# stepsticka4984.net
KiCad netlist of a schematic drawn in EAGLE
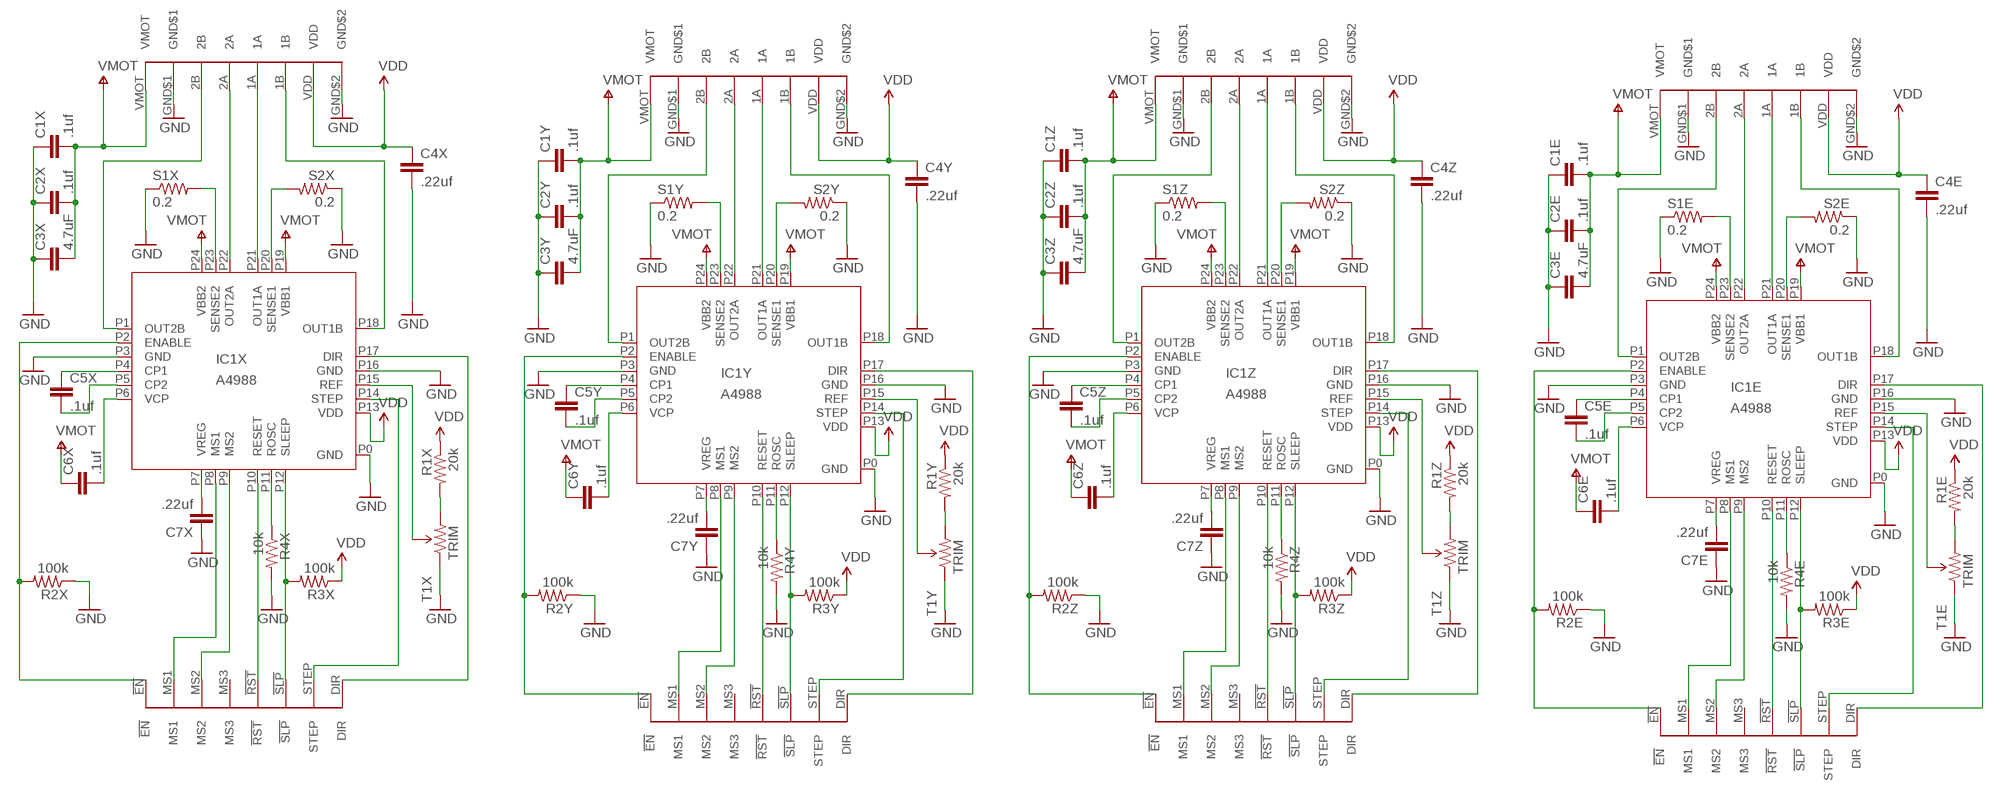
[diagram p0: schematic, sheet 1]

(export (version "E")
  (design (tool "Eeschema 10.0.6"))
  (components
    (comp (ref "C1E")
      (value ".1uf")
      (footprint "eagle-import:0402-CAP")
      (libsource (lib "eagle-import") (part "CAP0402-CAP"))
    )
    (comp (ref "C1X")
      (value ".1uf")
      (footprint "eagle-import:0402-CAP")
      (libsource (lib "eagle-import") (part "CAP0402-CAP"))
    )
    (comp (ref "C1Y")
      (value ".1uf")
      (footprint "eagle-import:0402-CAP")
      (libsource (lib "eagle-import") (part "CAP0402-CAP"))
    )
    (comp (ref "C1Z")
      (value ".1uf")
      (footprint "eagle-import:0402-CAP")
      (libsource (lib "eagle-import") (part "CAP0402-CAP"))
    )
    (comp (ref "C2E")
      (value ".1uf")
      (footprint "eagle-import:0402-CAP")
      (libsource (lib "eagle-import") (part "CAP0402-CAP"))
    )
    (comp (ref "C2X")
      (value ".1uf")
      (footprint "eagle-import:0402-CAP")
      (libsource (lib "eagle-import") (part "CAP0402-CAP"))
    )
    (comp (ref "C2Y")
      (value ".1uf")
      (footprint "eagle-import:0402-CAP")
      (libsource (lib "eagle-import") (part "CAP0402-CAP"))
    )
    (comp (ref "C2Z")
      (value ".1uf")
      (footprint "eagle-import:0402-CAP")
      (libsource (lib "eagle-import") (part "CAP0402-CAP"))
    )
    (comp (ref "C3E")
      (value "4.7uF")
      (footprint "eagle-import:1206")
      (libsource (lib "eagle-import") (part "CAP1206"))
    )
    (comp (ref "C3X")
      (value "4.7uF")
      (footprint "eagle-import:1206")
      (libsource (lib "eagle-import") (part "CAP1206"))
    )
    (comp (ref "C3Y")
      (value "4.7uF")
      (footprint "eagle-import:1206")
      (libsource (lib "eagle-import") (part "CAP1206"))
    )
    (comp (ref "C3Z")
      (value "4.7uF")
      (footprint "eagle-import:1206")
      (libsource (lib "eagle-import") (part "CAP1206"))
    )
    (comp (ref "C4E")
      (value ".22uf")
      (footprint "eagle-import:0402-CAP")
      (libsource (lib "eagle-import") (part "CAP0402-CAP"))
    )
    (comp (ref "C4X")
      (value ".22uf")
      (footprint "eagle-import:0402-CAP")
      (libsource (lib "eagle-import") (part "CAP0402-CAP"))
    )
    (comp (ref "C4Y")
      (value ".22uf")
      (footprint "eagle-import:0402-CAP")
      (libsource (lib "eagle-import") (part "CAP0402-CAP"))
    )
    (comp (ref "C4Z")
      (value ".22uf")
      (footprint "eagle-import:0402-CAP")
      (libsource (lib "eagle-import") (part "CAP0402-CAP"))
    )
    (comp (ref "C5E")
      (value ".1uf")
      (footprint "eagle-import:0402-CAP")
      (libsource (lib "eagle-import") (part "CAP0402-CAP"))
    )
    (comp (ref "C5X")
      (value ".1uf")
      (footprint "eagle-import:0402-CAP")
      (libsource (lib "eagle-import") (part "CAP0402-CAP"))
    )
    (comp (ref "C5Y")
      (value ".1uf")
      (footprint "eagle-import:0402-CAP")
      (libsource (lib "eagle-import") (part "CAP0402-CAP"))
    )
    (comp (ref "C5Z")
      (value ".1uf")
      (footprint "eagle-import:0402-CAP")
      (libsource (lib "eagle-import") (part "CAP0402-CAP"))
    )
    (comp (ref "C6E")
      (value ".1uf")
      (footprint "eagle-import:0402-CAP")
      (libsource (lib "eagle-import") (part "CAP0402-CAP"))
    )
    (comp (ref "C6X")
      (value ".1uf")
      (footprint "eagle-import:0402-CAP")
      (libsource (lib "eagle-import") (part "CAP0402-CAP"))
    )
    (comp (ref "C6Y")
      (value ".1uf")
      (footprint "eagle-import:0402-CAP")
      (libsource (lib "eagle-import") (part "CAP0402-CAP"))
    )
    (comp (ref "C6Z")
      (value ".1uf")
      (footprint "eagle-import:0402-CAP")
      (libsource (lib "eagle-import") (part "CAP0402-CAP"))
    )
    (comp (ref "C7E")
      (value ".22uf")
      (footprint "eagle-import:0402-CAP")
      (libsource (lib "eagle-import") (part "CAP0402-CAP"))
    )
    (comp (ref "C7X")
      (value ".22uf")
      (footprint "eagle-import:0402-CAP")
      (libsource (lib "eagle-import") (part "CAP0402-CAP"))
    )
    (comp (ref "C7Y")
      (value ".22uf")
      (footprint "eagle-import:0402-CAP")
      (libsource (lib "eagle-import") (part "CAP0402-CAP"))
    )
    (comp (ref "C7Z")
      (value ".22uf")
      (footprint "eagle-import:0402-CAP")
      (libsource (lib "eagle-import") (part "CAP0402-CAP"))
    )
    (comp (ref "IC1E")
      (value "A4988")
      (footprint "eagle-import:QFN24ES")
      (libsource (lib "eagle-import") (part "A4984"))
    )
    (comp (ref "IC1X")
      (value "A4988")
      (footprint "eagle-import:QFN24ES")
      (libsource (lib "eagle-import") (part "A4984"))
    )
    (comp (ref "IC1Y")
      (value "A4988")
      (footprint "eagle-import:QFN24ES")
      (libsource (lib "eagle-import") (part "A4984"))
    )
    (comp (ref "IC1Z")
      (value "A4988")
      (footprint "eagle-import:QFN24ES")
      (libsource (lib "eagle-import") (part "A4984"))
    )
    (comp (ref "J1E")
      (value "CLONOLU")
      (footprint "eagle-import:CLONOLU")
      (libsource (lib "eagle-import") (part "CLONOLU"))
    )
    (comp (ref "J1X")
      (value "CLONOLU")
      (footprint "eagle-import:CLONOLU")
      (libsource (lib "eagle-import") (part "CLONOLU"))
    )
    (comp (ref "J1Y")
      (value "CLONOLU")
      (footprint "eagle-import:CLONOLU")
      (libsource (lib "eagle-import") (part "CLONOLU"))
    )
    (comp (ref "J1Z")
      (value "CLONOLU")
      (footprint "eagle-import:CLONOLU")
      (libsource (lib "eagle-import") (part "CLONOLU"))
    )
    (comp (ref "R1E")
      (value "20k")
      (footprint "eagle-import:0402-RES")
      (libsource (lib "eagle-import") (part "RESISTOR0402-RES"))
    )
    (comp (ref "R1X")
      (value "20k")
      (footprint "eagle-import:0402-RES")
      (libsource (lib "eagle-import") (part "RESISTOR0402-RES"))
    )
    (comp (ref "R1Y")
      (value "20k")
      (footprint "eagle-import:0402-RES")
      (libsource (lib "eagle-import") (part "RESISTOR0402-RES"))
    )
    (comp (ref "R1Z")
      (value "20k")
      (footprint "eagle-import:0402-RES")
      (libsource (lib "eagle-import") (part "RESISTOR0402-RES"))
    )
    (comp (ref "R2E")
      (value "100k")
      (footprint "eagle-import:0402-RES")
      (libsource (lib "eagle-import") (part "RESISTOR0402-RES"))
    )
    (comp (ref "R2X")
      (value "100k")
      (footprint "eagle-import:0402-RES")
      (libsource (lib "eagle-import") (part "RESISTOR0402-RES"))
    )
    (comp (ref "R2Y")
      (value "100k")
      (footprint "eagle-import:0402-RES")
      (libsource (lib "eagle-import") (part "RESISTOR0402-RES"))
    )
    (comp (ref "R2Z")
      (value "100k")
      (footprint "eagle-import:0402-RES")
      (libsource (lib "eagle-import") (part "RESISTOR0402-RES"))
    )
    (comp (ref "R3E")
      (value "100k")
      (footprint "eagle-import:0402-RES")
      (libsource (lib "eagle-import") (part "RESISTOR0402-RES"))
    )
    (comp (ref "R3X")
      (value "100k")
      (footprint "eagle-import:0402-RES")
      (libsource (lib "eagle-import") (part "RESISTOR0402-RES"))
    )
    (comp (ref "R3Y")
      (value "100k")
      (footprint "eagle-import:0402-RES")
      (libsource (lib "eagle-import") (part "RESISTOR0402-RES"))
    )
    (comp (ref "R3Z")
      (value "100k")
      (footprint "eagle-import:0402-RES")
      (libsource (lib "eagle-import") (part "RESISTOR0402-RES"))
    )
    (comp (ref "R4E")
      (value "10k")
      (footprint "eagle-import:0402-RES")
      (libsource (lib "eagle-import") (part "RESISTOR0402-RES"))
    )
    (comp (ref "R4X")
      (value "10k")
      (footprint "eagle-import:0402-RES")
      (libsource (lib "eagle-import") (part "RESISTOR0402-RES"))
    )
    (comp (ref "R4Y")
      (value "10k")
      (footprint "eagle-import:0402-RES")
      (libsource (lib "eagle-import") (part "RESISTOR0402-RES"))
    )
    (comp (ref "R4Z")
      (value "10k")
      (footprint "eagle-import:0402-RES")
      (libsource (lib "eagle-import") (part "RESISTOR0402-RES"))
    )
    (comp (ref "S1E")
      (value "0.2")
      (footprint "eagle-import:0805")
      (libsource (lib "eagle-import") (part "RESISTOR"))
    )
    (comp (ref "S1X")
      (value "0.2")
      (footprint "eagle-import:0805")
      (libsource (lib "eagle-import") (part "RESISTOR"))
    )
    (comp (ref "S1Y")
      (value "0.2")
      (footprint "eagle-import:0805")
      (libsource (lib "eagle-import") (part "RESISTOR"))
    )
    (comp (ref "S1Z")
      (value "0.2")
      (footprint "eagle-import:0805")
      (libsource (lib "eagle-import") (part "RESISTOR"))
    )
    (comp (ref "S2E")
      (value "0.2")
      (footprint "eagle-import:0805")
      (libsource (lib "eagle-import") (part "RESISTOR"))
    )
    (comp (ref "S2X")
      (value "0.2")
      (footprint "eagle-import:0805")
      (libsource (lib "eagle-import") (part "RESISTOR"))
    )
    (comp (ref "S2Y")
      (value "0.2")
      (footprint "eagle-import:0805")
      (libsource (lib "eagle-import") (part "RESISTOR"))
    )
    (comp (ref "S2Z")
      (value "0.2")
      (footprint "eagle-import:0805")
      (libsource (lib "eagle-import") (part "RESISTOR"))
    )
    (comp (ref "T1E")
      (value "TRIM")
      (footprint "eagle-import:TRIMPOT-3MM")
      (libsource (lib "eagle-import") (part "TRIMPOTSMD"))
    )
    (comp (ref "T1X")
      (value "TRIM")
      (footprint "eagle-import:TRIMPOT-3MM")
      (libsource (lib "eagle-import") (part "TRIMPOTSMD"))
    )
    (comp (ref "T1Y")
      (value "TRIM")
      (footprint "eagle-import:TRIMPOT-3MM")
      (libsource (lib "eagle-import") (part "TRIMPOTSMD"))
    )
    (comp (ref "T1Z")
      (value "TRIM")
      (footprint "eagle-import:TRIMPOT-3MM")
      (libsource (lib "eagle-import") (part "TRIMPOTSMD"))
    )
  )
  (nets
    (net (code "1") (name "GND") (class "Default")
      (node (ref "C1E") (pin "1") (pinfunction "1_1") (pintype "passive"))
      (node (ref "C1X") (pin "1") (pinfunction "1_1") (pintype "passive"))
      (node (ref "C1Y") (pin "1") (pinfunction "1_1") (pintype "passive"))
      (node (ref "C1Z") (pin "1") (pinfunction "1_1") (pintype "passive"))
      (node (ref "C2E") (pin "1") (pinfunction "1_1") (pintype "passive"))
      (node (ref "C2X") (pin "1") (pinfunction "1_1") (pintype "passive"))
      (node (ref "C2Y") (pin "1") (pinfunction "1_1") (pintype "passive"))
      (node (ref "C2Z") (pin "1") (pinfunction "1_1") (pintype "passive"))
      (node (ref "C3E") (pin "1") (pinfunction "1_1") (pintype "passive"))
      (node (ref "C3X") (pin "1") (pinfunction "1_1") (pintype "passive"))
      (node (ref "C3Y") (pin "1") (pinfunction "1_1") (pintype "passive"))
      (node (ref "C3Z") (pin "1") (pinfunction "1_1") (pintype "passive"))
      (node (ref "C4E") (pin "2") (pinfunction "2_2") (pintype "passive"))
      (node (ref "C4X") (pin "2") (pinfunction "2_2") (pintype "passive"))
      (node (ref "C4Y") (pin "2") (pinfunction "2_2") (pintype "passive"))
      (node (ref "C4Z") (pin "2") (pinfunction "2_2") (pintype "passive"))
      (node (ref "C7E") (pin "1") (pinfunction "1_1") (pintype "passive"))
      (node (ref "C7X") (pin "1") (pinfunction "1_1") (pintype "passive"))
      (node (ref "C7Y") (pin "1") (pinfunction "1_1") (pintype "passive"))
      (node (ref "C7Z") (pin "1") (pinfunction "1_1") (pintype "passive"))
      (node (ref "IC1E") (pin "P0") (pinfunction "GND_P0") (pintype "bidirectional"))
      (node (ref "IC1E") (pin "P16") (pinfunction "GND_P16") (pintype "power_in"))
      (node (ref "IC1E") (pin "P3") (pinfunction "GND_P3") (pintype "power_in"))
      (node (ref "IC1X") (pin "P0") (pinfunction "GND_P0") (pintype "bidirectional"))
      (node (ref "IC1X") (pin "P16") (pinfunction "GND_P16") (pintype "power_in"))
      (node (ref "IC1X") (pin "P3") (pinfunction "GND_P3") (pintype "power_in"))
      (node (ref "IC1Y") (pin "P0") (pinfunction "GND_P0") (pintype "bidirectional"))
      (node (ref "IC1Y") (pin "P16") (pinfunction "GND_P16") (pintype "power_in"))
      (node (ref "IC1Y") (pin "P3") (pinfunction "GND_P3") (pintype "power_in"))
      (node (ref "IC1Z") (pin "P0") (pinfunction "GND_P0") (pintype "bidirectional"))
      (node (ref "IC1Z") (pin "P16") (pinfunction "GND_P16") (pintype "power_in"))
      (node (ref "IC1Z") (pin "P3") (pinfunction "GND_P3") (pintype "power_in"))
      (node (ref "J1E") (pin "GND$1") (pinfunction "GND$1_GND$1") (pintype "power_in"))
      (node (ref "J1E") (pin "GND$2") (pinfunction "GND$2_GND$2") (pintype "power_in"))
      (node (ref "J1X") (pin "GND$1") (pinfunction "GND$1_GND$1") (pintype "power_in"))
      (node (ref "J1X") (pin "GND$2") (pinfunction "GND$2_GND$2") (pintype "power_in"))
      (node (ref "J1Y") (pin "GND$1") (pinfunction "GND$1_GND$1") (pintype "power_in"))
      (node (ref "J1Y") (pin "GND$2") (pinfunction "GND$2_GND$2") (pintype "power_in"))
      (node (ref "J1Z") (pin "GND$1") (pinfunction "GND$1_GND$1") (pintype "power_in"))
      (node (ref "J1Z") (pin "GND$2") (pinfunction "GND$2_GND$2") (pintype "power_in"))
      (node (ref "R2E") (pin "1") (pinfunction "1_1") (pintype "passive"))
      (node (ref "R2X") (pin "1") (pinfunction "1_1") (pintype "passive"))
      (node (ref "R2Y") (pin "1") (pinfunction "1_1") (pintype "passive"))
      (node (ref "R2Z") (pin "1") (pinfunction "1_1") (pintype "passive"))
      (node (ref "R4E") (pin "2") (pinfunction "2_2") (pintype "passive"))
      (node (ref "R4X") (pin "2") (pinfunction "2_2") (pintype "passive"))
      (node (ref "R4Y") (pin "2") (pinfunction "2_2") (pintype "passive"))
      (node (ref "R4Z") (pin "2") (pinfunction "2_2") (pintype "passive"))
      (node (ref "S1E") (pin "1") (pinfunction "1_1") (pintype "passive"))
      (node (ref "S1X") (pin "1") (pinfunction "1_1") (pintype "passive"))
      (node (ref "S1Y") (pin "1") (pinfunction "1_1") (pintype "passive"))
      (node (ref "S1Z") (pin "1") (pinfunction "1_1") (pintype "passive"))
      (node (ref "S2E") (pin "1") (pinfunction "1_1") (pintype "passive"))
      (node (ref "S2X") (pin "1") (pinfunction "1_1") (pintype "passive"))
      (node (ref "S2Y") (pin "1") (pinfunction "1_1") (pintype "passive"))
      (node (ref "S2Z") (pin "1") (pinfunction "1_1") (pintype "passive"))
      (node (ref "T1E") (pin "1") (pinfunction "CCW_1") (pintype "passive"))
      (node (ref "T1X") (pin "1") (pinfunction "CCW_1") (pintype "passive"))
      (node (ref "T1Y") (pin "1") (pinfunction "CCW_1") (pintype "passive"))
      (node (ref "T1Z") (pin "1") (pinfunction "CCW_1") (pintype "passive"))
    )
    (net (code "2") (name "Net-(IC1E-CP1)") (class "Default")
      (node (ref "C5E") (pin "1") (pinfunction "1_1") (pintype "passive"))
      (node (ref "IC1E") (pin "P4") (pinfunction "CP1_P4") (pintype "passive"))
    )
    (net (code "3") (name "Net-(IC1E-CP2)") (class "Default")
      (node (ref "C5E") (pin "2") (pinfunction "2_2") (pintype "passive"))
      (node (ref "IC1E") (pin "P5") (pinfunction "CP2_P5") (pintype "passive"))
    )
    (net (code "4") (name "Net-(IC1E-DIR)") (class "Default")
      (node (ref "IC1E") (pin "P17") (pinfunction "DIR_P17") (pintype "input"))
      (node (ref "J1E") (pin "DIR") (pinfunction "DIR_DIR") (pintype "bidirectional"))
    )
    (net (code "5") (name "Net-(IC1E-ENABLE)") (class "Default")
      (node (ref "IC1E") (pin "P2") (pinfunction "ENABLE_P2") (pintype "input"))
      (node (ref "J1E") (pin "!EN") (pinfunction "~{EN}_!EN") (pintype "bidirectional"))
      (node (ref "R2E") (pin "2") (pinfunction "2_2") (pintype "passive"))
    )
    (net (code "6") (name "Net-(IC1E-MS1)") (class "Default")
      (node (ref "IC1E") (pin "P8") (pinfunction "MS1_P8") (pintype "input"))
      (node (ref "J1E") (pin "MS1") (pinfunction "MS1_MS1") (pintype "bidirectional"))
    )
    (net (code "7") (name "Net-(IC1E-MS2)") (class "Default")
      (node (ref "IC1E") (pin "P9") (pinfunction "MS2_P9") (pintype "input"))
      (node (ref "J1E") (pin "MS2") (pinfunction "MS2_MS2") (pintype "bidirectional"))
    )
    (net (code "8") (name "Net-(IC1E-OUT1A)") (class "Default")
      (node (ref "IC1E") (pin "P21") (pinfunction "OUT1A_P21") (pintype "output"))
      (node (ref "J1E") (pin "1A") (pinfunction "1A_1A") (pintype "bidirectional"))
    )
    (net (code "9") (name "Net-(IC1E-OUT1B)") (class "Default")
      (node (ref "IC1E") (pin "P18") (pinfunction "OUT1B_P18") (pintype "output"))
      (node (ref "J1E") (pin "1B") (pinfunction "1B_1B") (pintype "bidirectional"))
    )
    (net (code "10") (name "Net-(IC1E-OUT2A)") (class "Default")
      (node (ref "IC1E") (pin "P22") (pinfunction "OUT2A_P22") (pintype "output"))
      (node (ref "J1E") (pin "2A") (pinfunction "2A_2A") (pintype "bidirectional"))
    )
    (net (code "11") (name "Net-(IC1E-OUT2B)") (class "Default")
      (node (ref "IC1E") (pin "P1") (pinfunction "OUT2B_P1") (pintype "output"))
      (node (ref "J1E") (pin "2B") (pinfunction "2B_2B") (pintype "bidirectional"))
    )
    (net (code "12") (name "Net-(IC1E-REF)") (class "Default")
      (node (ref "IC1E") (pin "P15") (pinfunction "REF_P15") (pintype "input"))
      (node (ref "T1E") (pin "2") (pinfunction "WIPER_2") (pintype "passive"))
    )
    (net (code "13") (name "Net-(IC1E-RESET)") (class "Default")
      (node (ref "IC1E") (pin "P10") (pinfunction "RESET_P10") (pintype "input"))
      (node (ref "J1E") (pin "!RST") (pinfunction "~{RST}_!RST") (pintype "bidirectional"))
    )
    (net (code "14") (name "Net-(IC1E-ROSC)") (class "Default")
      (node (ref "IC1E") (pin "P11") (pinfunction "ROSC_P11") (pintype "input"))
      (node (ref "R4E") (pin "1") (pinfunction "1_1") (pintype "passive"))
    )
    (net (code "15") (name "Net-(IC1E-SENSE1)") (class "Default")
      (node (ref "IC1E") (pin "P20") (pinfunction "SENSE1_P20") (pintype "input"))
      (node (ref "S2E") (pin "2") (pinfunction "2_2") (pintype "passive"))
    )
    (net (code "16") (name "Net-(IC1E-SENSE2)") (class "Default")
      (node (ref "IC1E") (pin "P23") (pinfunction "SENSE2_P23") (pintype "input"))
      (node (ref "S1E") (pin "2") (pinfunction "2_2") (pintype "passive"))
    )
    (net (code "17") (name "Net-(IC1E-SLEEP)") (class "Default")
      (node (ref "IC1E") (pin "P12") (pinfunction "SLEEP_P12") (pintype "input"))
      (node (ref "J1E") (pin "!SLP") (pinfunction "~{SLP}_!SLP") (pintype "bidirectional"))
      (node (ref "R3E") (pin "2") (pinfunction "2_2") (pintype "passive"))
    )
    (net (code "18") (name "Net-(IC1E-STEP)") (class "Default")
      (node (ref "IC1E") (pin "P14") (pinfunction "STEP_P14") (pintype "input"))
      (node (ref "J1E") (pin "STEP") (pinfunction "STEP_STEP") (pintype "bidirectional"))
    )
    (net (code "19") (name "Net-(IC1E-VCP)") (class "Default")
      (node (ref "C6E") (pin "2") (pinfunction "2_2") (pintype "passive"))
      (node (ref "IC1E") (pin "P6") (pinfunction "VCP_P6") (pintype "passive"))
    )
    (net (code "20") (name "Net-(IC1E-VREG)") (class "Default")
      (node (ref "C7E") (pin "2") (pinfunction "2_2") (pintype "passive"))
      (node (ref "IC1E") (pin "P7") (pinfunction "VREG_P7") (pintype "passive"))
    )
    (net (code "21") (name "Net-(IC1X-CP1)") (class "Default")
      (node (ref "C5X") (pin "1") (pinfunction "1_1") (pintype "passive"))
      (node (ref "IC1X") (pin "P4") (pinfunction "CP1_P4") (pintype "passive"))
    )
    (net (code "22") (name "Net-(IC1X-CP2)") (class "Default")
      (node (ref "C5X") (pin "2") (pinfunction "2_2") (pintype "passive"))
      (node (ref "IC1X") (pin "P5") (pinfunction "CP2_P5") (pintype "passive"))
    )
    (net (code "23") (name "Net-(IC1X-DIR)") (class "Default")
      (node (ref "IC1X") (pin "P17") (pinfunction "DIR_P17") (pintype "input"))
      (node (ref "J1X") (pin "DIR") (pinfunction "DIR_DIR") (pintype "bidirectional"))
    )
    (net (code "24") (name "Net-(IC1X-ENABLE)") (class "Default")
      (node (ref "IC1X") (pin "P2") (pinfunction "ENABLE_P2") (pintype "input"))
      (node (ref "J1X") (pin "!EN") (pinfunction "~{EN}_!EN") (pintype "bidirectional"))
      (node (ref "R2X") (pin "2") (pinfunction "2_2") (pintype "passive"))
    )
    (net (code "25") (name "Net-(IC1X-MS1)") (class "Default")
      (node (ref "IC1X") (pin "P8") (pinfunction "MS1_P8") (pintype "input"))
      (node (ref "J1X") (pin "MS1") (pinfunction "MS1_MS1") (pintype "bidirectional"))
    )
    (net (code "26") (name "Net-(IC1X-MS2)") (class "Default")
      (node (ref "IC1X") (pin "P9") (pinfunction "MS2_P9") (pintype "input"))
      (node (ref "J1X") (pin "MS2") (pinfunction "MS2_MS2") (pintype "bidirectional"))
    )
    (net (code "27") (name "Net-(IC1X-OUT1A)") (class "Default")
      (node (ref "IC1X") (pin "P21") (pinfunction "OUT1A_P21") (pintype "output"))
      (node (ref "J1X") (pin "1A") (pinfunction "1A_1A") (pintype "bidirectional"))
    )
    (net (code "28") (name "Net-(IC1X-OUT1B)") (class "Default")
      (node (ref "IC1X") (pin "P18") (pinfunction "OUT1B_P18") (pintype "output"))
      (node (ref "J1X") (pin "1B") (pinfunction "1B_1B") (pintype "bidirectional"))
    )
    (net (code "29") (name "Net-(IC1X-OUT2A)") (class "Default")
      (node (ref "IC1X") (pin "P22") (pinfunction "OUT2A_P22") (pintype "output"))
      (node (ref "J1X") (pin "2A") (pinfunction "2A_2A") (pintype "bidirectional"))
    )
    (net (code "30") (name "Net-(IC1X-OUT2B)") (class "Default")
      (node (ref "IC1X") (pin "P1") (pinfunction "OUT2B_P1") (pintype "output"))
      (node (ref "J1X") (pin "2B") (pinfunction "2B_2B") (pintype "bidirectional"))
    )
    (net (code "31") (name "Net-(IC1X-REF)") (class "Default")
      (node (ref "IC1X") (pin "P15") (pinfunction "REF_P15") (pintype "input"))
      (node (ref "T1X") (pin "2") (pinfunction "WIPER_2") (pintype "passive"))
    )
    (net (code "32") (name "Net-(IC1X-RESET)") (class "Default")
      (node (ref "IC1X") (pin "P10") (pinfunction "RESET_P10") (pintype "input"))
      (node (ref "J1X") (pin "!RST") (pinfunction "~{RST}_!RST") (pintype "bidirectional"))
    )
    (net (code "33") (name "Net-(IC1X-ROSC)") (class "Default")
      (node (ref "IC1X") (pin "P11") (pinfunction "ROSC_P11") (pintype "input"))
      (node (ref "R4X") (pin "1") (pinfunction "1_1") (pintype "passive"))
    )
    (net (code "34") (name "Net-(IC1X-SENSE1)") (class "Default")
      (node (ref "IC1X") (pin "P20") (pinfunction "SENSE1_P20") (pintype "input"))
      (node (ref "S2X") (pin "2") (pinfunction "2_2") (pintype "passive"))
    )
    (net (code "35") (name "Net-(IC1X-SENSE2)") (class "Default")
      (node (ref "IC1X") (pin "P23") (pinfunction "SENSE2_P23") (pintype "input"))
      (node (ref "S1X") (pin "2") (pinfunction "2_2") (pintype "passive"))
    )
    (net (code "36") (name "Net-(IC1X-SLEEP)") (class "Default")
      (node (ref "IC1X") (pin "P12") (pinfunction "SLEEP_P12") (pintype "input"))
      (node (ref "J1X") (pin "!SLP") (pinfunction "~{SLP}_!SLP") (pintype "bidirectional"))
      (node (ref "R3X") (pin "2") (pinfunction "2_2") (pintype "passive"))
    )
    (net (code "37") (name "Net-(IC1X-STEP)") (class "Default")
      (node (ref "IC1X") (pin "P14") (pinfunction "STEP_P14") (pintype "input"))
      (node (ref "J1X") (pin "STEP") (pinfunction "STEP_STEP") (pintype "bidirectional"))
    )
    (net (code "38") (name "Net-(IC1X-VCP)") (class "Default")
      (node (ref "C6X") (pin "2") (pinfunction "2_2") (pintype "passive"))
      (node (ref "IC1X") (pin "P6") (pinfunction "VCP_P6") (pintype "passive"))
    )
    (net (code "39") (name "Net-(IC1X-VREG)") (class "Default")
      (node (ref "C7X") (pin "2") (pinfunction "2_2") (pintype "passive"))
      (node (ref "IC1X") (pin "P7") (pinfunction "VREG_P7") (pintype "passive"))
    )
    (net (code "40") (name "Net-(IC1Y-CP1)") (class "Default")
      (node (ref "C5Y") (pin "1") (pinfunction "1_1") (pintype "passive"))
      (node (ref "IC1Y") (pin "P4") (pinfunction "CP1_P4") (pintype "passive"))
    )
    (net (code "41") (name "Net-(IC1Y-CP2)") (class "Default")
      (node (ref "C5Y") (pin "2") (pinfunction "2_2") (pintype "passive"))
      (node (ref "IC1Y") (pin "P5") (pinfunction "CP2_P5") (pintype "passive"))
    )
    (net (code "42") (name "Net-(IC1Y-DIR)") (class "Default")
      (node (ref "IC1Y") (pin "P17") (pinfunction "DIR_P17") (pintype "input"))
      (node (ref "J1Y") (pin "DIR") (pinfunction "DIR_DIR") (pintype "bidirectional"))
    )
    (net (code "43") (name "Net-(IC1Y-ENABLE)") (class "Default")
      (node (ref "IC1Y") (pin "P2") (pinfunction "ENABLE_P2") (pintype "input"))
      (node (ref "J1Y") (pin "!EN") (pinfunction "~{EN}_!EN") (pintype "bidirectional"))
      (node (ref "R2Y") (pin "2") (pinfunction "2_2") (pintype "passive"))
    )
    (net (code "44") (name "Net-(IC1Y-MS1)") (class "Default")
      (node (ref "IC1Y") (pin "P8") (pinfunction "MS1_P8") (pintype "input"))
      (node (ref "J1Y") (pin "MS1") (pinfunction "MS1_MS1") (pintype "bidirectional"))
    )
    (net (code "45") (name "Net-(IC1Y-MS2)") (class "Default")
      (node (ref "IC1Y") (pin "P9") (pinfunction "MS2_P9") (pintype "input"))
      (node (ref "J1Y") (pin "MS2") (pinfunction "MS2_MS2") (pintype "bidirectional"))
    )
    (net (code "46") (name "Net-(IC1Y-OUT1A)") (class "Default")
      (node (ref "IC1Y") (pin "P21") (pinfunction "OUT1A_P21") (pintype "output"))
      (node (ref "J1Y") (pin "1A") (pinfunction "1A_1A") (pintype "bidirectional"))
    )
    (net (code "47") (name "Net-(IC1Y-OUT1B)") (class "Default")
      (node (ref "IC1Y") (pin "P18") (pinfunction "OUT1B_P18") (pintype "output"))
      (node (ref "J1Y") (pin "1B") (pinfunction "1B_1B") (pintype "bidirectional"))
    )
    (net (code "48") (name "Net-(IC1Y-OUT2A)") (class "Default")
      (node (ref "IC1Y") (pin "P22") (pinfunction "OUT2A_P22") (pintype "output"))
      (node (ref "J1Y") (pin "2A") (pinfunction "2A_2A") (pintype "bidirectional"))
    )
    (net (code "49") (name "Net-(IC1Y-OUT2B)") (class "Default")
      (node (ref "IC1Y") (pin "P1") (pinfunction "OUT2B_P1") (pintype "output"))
      (node (ref "J1Y") (pin "2B") (pinfunction "2B_2B") (pintype "bidirectional"))
    )
    (net (code "50") (name "Net-(IC1Y-REF)") (class "Default")
      (node (ref "IC1Y") (pin "P15") (pinfunction "REF_P15") (pintype "input"))
      (node (ref "T1Y") (pin "2") (pinfunction "WIPER_2") (pintype "passive"))
    )
    (net (code "51") (name "Net-(IC1Y-RESET)") (class "Default")
      (node (ref "IC1Y") (pin "P10") (pinfunction "RESET_P10") (pintype "input"))
      (node (ref "J1Y") (pin "!RST") (pinfunction "~{RST}_!RST") (pintype "bidirectional"))
    )
    (net (code "52") (name "Net-(IC1Y-ROSC)") (class "Default")
      (node (ref "IC1Y") (pin "P11") (pinfunction "ROSC_P11") (pintype "input"))
      (node (ref "R4Y") (pin "1") (pinfunction "1_1") (pintype "passive"))
    )
    (net (code "53") (name "Net-(IC1Y-SENSE1)") (class "Default")
      (node (ref "IC1Y") (pin "P20") (pinfunction "SENSE1_P20") (pintype "input"))
      (node (ref "S2Y") (pin "2") (pinfunction "2_2") (pintype "passive"))
    )
    (net (code "54") (name "Net-(IC1Y-SENSE2)") (class "Default")
      (node (ref "IC1Y") (pin "P23") (pinfunction "SENSE2_P23") (pintype "input"))
      (node (ref "S1Y") (pin "2") (pinfunction "2_2") (pintype "passive"))
    )
    (net (code "55") (name "Net-(IC1Y-SLEEP)") (class "Default")
      (node (ref "IC1Y") (pin "P12") (pinfunction "SLEEP_P12") (pintype "input"))
      (node (ref "J1Y") (pin "!SLP") (pinfunction "~{SLP}_!SLP") (pintype "bidirectional"))
      (node (ref "R3Y") (pin "2") (pinfunction "2_2") (pintype "passive"))
    )
    (net (code "56") (name "Net-(IC1Y-STEP)") (class "Default")
      (node (ref "IC1Y") (pin "P14") (pinfunction "STEP_P14") (pintype "input"))
      (node (ref "J1Y") (pin "STEP") (pinfunction "STEP_STEP") (pintype "bidirectional"))
    )
    (net (code "57") (name "Net-(IC1Y-VCP)") (class "Default")
      (node (ref "C6Y") (pin "2") (pinfunction "2_2") (pintype "passive"))
      (node (ref "IC1Y") (pin "P6") (pinfunction "VCP_P6") (pintype "passive"))
    )
    (net (code "58") (name "Net-(IC1Y-VREG)") (class "Default")
      (node (ref "C7Y") (pin "2") (pinfunction "2_2") (pintype "passive"))
      (node (ref "IC1Y") (pin "P7") (pinfunction "VREG_P7") (pintype "passive"))
    )
    (net (code "59") (name "Net-(IC1Z-CP1)") (class "Default")
      (node (ref "C5Z") (pin "1") (pinfunction "1_1") (pintype "passive"))
      (node (ref "IC1Z") (pin "P4") (pinfunction "CP1_P4") (pintype "passive"))
    )
    (net (code "60") (name "Net-(IC1Z-CP2)") (class "Default")
      (node (ref "C5Z") (pin "2") (pinfunction "2_2") (pintype "passive"))
      (node (ref "IC1Z") (pin "P5") (pinfunction "CP2_P5") (pintype "passive"))
    )
    (net (code "61") (name "Net-(IC1Z-DIR)") (class "Default")
      (node (ref "IC1Z") (pin "P17") (pinfunction "DIR_P17") (pintype "input"))
      (node (ref "J1Z") (pin "DIR") (pinfunction "DIR_DIR") (pintype "bidirectional"))
    )
    (net (code "62") (name "Net-(IC1Z-ENABLE)") (class "Default")
      (node (ref "IC1Z") (pin "P2") (pinfunction "ENABLE_P2") (pintype "input"))
      (node (ref "J1Z") (pin "!EN") (pinfunction "~{EN}_!EN") (pintype "bidirectional"))
      (node (ref "R2Z") (pin "2") (pinfunction "2_2") (pintype "passive"))
    )
    (net (code "63") (name "Net-(IC1Z-MS1)") (class "Default")
      (node (ref "IC1Z") (pin "P8") (pinfunction "MS1_P8") (pintype "input"))
      (node (ref "J1Z") (pin "MS1") (pinfunction "MS1_MS1") (pintype "bidirectional"))
    )
    (net (code "64") (name "Net-(IC1Z-MS2)") (class "Default")
      (node (ref "IC1Z") (pin "P9") (pinfunction "MS2_P9") (pintype "input"))
      (node (ref "J1Z") (pin "MS2") (pinfunction "MS2_MS2") (pintype "bidirectional"))
    )
    (net (code "65") (name "Net-(IC1Z-OUT1A)") (class "Default")
      (node (ref "IC1Z") (pin "P21") (pinfunction "OUT1A_P21") (pintype "output"))
      (node (ref "J1Z") (pin "1A") (pinfunction "1A_1A") (pintype "bidirectional"))
    )
    (net (code "66") (name "Net-(IC1Z-OUT1B)") (class "Default")
      (node (ref "IC1Z") (pin "P18") (pinfunction "OUT1B_P18") (pintype "output"))
      (node (ref "J1Z") (pin "1B") (pinfunction "1B_1B") (pintype "bidirectional"))
    )
    (net (code "67") (name "Net-(IC1Z-OUT2A)") (class "Default")
      (node (ref "IC1Z") (pin "P22") (pinfunction "OUT2A_P22") (pintype "output"))
      (node (ref "J1Z") (pin "2A") (pinfunction "2A_2A") (pintype "bidirectional"))
    )
    (net (code "68") (name "Net-(IC1Z-OUT2B)") (class "Default")
      (node (ref "IC1Z") (pin "P1") (pinfunction "OUT2B_P1") (pintype "output"))
      (node (ref "J1Z") (pin "2B") (pinfunction "2B_2B") (pintype "bidirectional"))
    )
    (net (code "69") (name "Net-(IC1Z-REF)") (class "Default")
      (node (ref "IC1Z") (pin "P15") (pinfunction "REF_P15") (pintype "input"))
      (node (ref "T1Z") (pin "2") (pinfunction "WIPER_2") (pintype "passive"))
    )
    (net (code "70") (name "Net-(IC1Z-RESET)") (class "Default")
      (node (ref "IC1Z") (pin "P10") (pinfunction "RESET_P10") (pintype "input"))
      (node (ref "J1Z") (pin "!RST") (pinfunction "~{RST}_!RST") (pintype "bidirectional"))
    )
    (net (code "71") (name "Net-(IC1Z-ROSC)") (class "Default")
      (node (ref "IC1Z") (pin "P11") (pinfunction "ROSC_P11") (pintype "input"))
      (node (ref "R4Z") (pin "1") (pinfunction "1_1") (pintype "passive"))
    )
    (net (code "72") (name "Net-(IC1Z-SENSE1)") (class "Default")
      (node (ref "IC1Z") (pin "P20") (pinfunction "SENSE1_P20") (pintype "input"))
      (node (ref "S2Z") (pin "2") (pinfunction "2_2") (pintype "passive"))
    )
    (net (code "73") (name "Net-(IC1Z-SENSE2)") (class "Default")
      (node (ref "IC1Z") (pin "P23") (pinfunction "SENSE2_P23") (pintype "input"))
      (node (ref "S1Z") (pin "2") (pinfunction "2_2") (pintype "passive"))
    )
    (net (code "74") (name "Net-(IC1Z-SLEEP)") (class "Default")
      (node (ref "IC1Z") (pin "P12") (pinfunction "SLEEP_P12") (pintype "input"))
      (node (ref "J1Z") (pin "!SLP") (pinfunction "~{SLP}_!SLP") (pintype "bidirectional"))
      (node (ref "R3Z") (pin "2") (pinfunction "2_2") (pintype "passive"))
    )
    (net (code "75") (name "Net-(IC1Z-STEP)") (class "Default")
      (node (ref "IC1Z") (pin "P14") (pinfunction "STEP_P14") (pintype "input"))
      (node (ref "J1Z") (pin "STEP") (pinfunction "STEP_STEP") (pintype "bidirectional"))
    )
    (net (code "76") (name "Net-(IC1Z-VCP)") (class "Default")
      (node (ref "C6Z") (pin "2") (pinfunction "2_2") (pintype "passive"))
      (node (ref "IC1Z") (pin "P6") (pinfunction "VCP_P6") (pintype "passive"))
    )
    (net (code "77") (name "Net-(IC1Z-VREG)") (class "Default")
      (node (ref "C7Z") (pin "2") (pinfunction "2_2") (pintype "passive"))
      (node (ref "IC1Z") (pin "P7") (pinfunction "VREG_P7") (pintype "passive"))
    )
    (net (code "78") (name "Net-(T1E-CW)") (class "Default")
      (node (ref "R1E") (pin "2") (pinfunction "2_2") (pintype "passive"))
      (node (ref "T1E") (pin "3") (pinfunction "CW_3") (pintype "passive"))
    )
    (net (code "79") (name "Net-(T1X-CW)") (class "Default")
      (node (ref "R1X") (pin "2") (pinfunction "2_2") (pintype "passive"))
      (node (ref "T1X") (pin "3") (pinfunction "CW_3") (pintype "passive"))
    )
    (net (code "80") (name "Net-(T1Y-CW)") (class "Default")
      (node (ref "R1Y") (pin "2") (pinfunction "2_2") (pintype "passive"))
      (node (ref "T1Y") (pin "3") (pinfunction "CW_3") (pintype "passive"))
    )
    (net (code "81") (name "Net-(T1Z-CW)") (class "Default")
      (node (ref "R1Z") (pin "2") (pinfunction "2_2") (pintype "passive"))
      (node (ref "T1Z") (pin "3") (pinfunction "CW_3") (pintype "passive"))
    )
    (net (code "82") (name "VDD") (class "Default")
      (node (ref "C4E") (pin "1") (pinfunction "1_1") (pintype "passive"))
      (node (ref "C4X") (pin "1") (pinfunction "1_1") (pintype "passive"))
      (node (ref "C4Y") (pin "1") (pinfunction "1_1") (pintype "passive"))
      (node (ref "C4Z") (pin "1") (pinfunction "1_1") (pintype "passive"))
      (node (ref "IC1E") (pin "P13") (pinfunction "VDD_P13") (pintype "power_in"))
      (node (ref "IC1X") (pin "P13") (pinfunction "VDD_P13") (pintype "power_in"))
      (node (ref "IC1Y") (pin "P13") (pinfunction "VDD_P13") (pintype "power_in"))
      (node (ref "IC1Z") (pin "P13") (pinfunction "VDD_P13") (pintype "power_in"))
      (node (ref "J1E") (pin "VDD") (pinfunction "VDD_VDD") (pintype "power_in"))
      (node (ref "J1X") (pin "VDD") (pinfunction "VDD_VDD") (pintype "power_in"))
      (node (ref "J1Y") (pin "VDD") (pinfunction "VDD_VDD") (pintype "power_in"))
      (node (ref "J1Z") (pin "VDD") (pinfunction "VDD_VDD") (pintype "power_in"))
      (node (ref "R1E") (pin "1") (pinfunction "1_1") (pintype "passive"))
      (node (ref "R1X") (pin "1") (pinfunction "1_1") (pintype "passive"))
      (node (ref "R1Y") (pin "1") (pinfunction "1_1") (pintype "passive"))
      (node (ref "R1Z") (pin "1") (pinfunction "1_1") (pintype "passive"))
      (node (ref "R3E") (pin "1") (pinfunction "1_1") (pintype "passive"))
      (node (ref "R3X") (pin "1") (pinfunction "1_1") (pintype "passive"))
      (node (ref "R3Y") (pin "1") (pinfunction "1_1") (pintype "passive"))
      (node (ref "R3Z") (pin "1") (pinfunction "1_1") (pintype "passive"))
    )
    (net (code "83") (name "VMOT") (class "Default")
      (node (ref "C1E") (pin "2") (pinfunction "2_2") (pintype "passive"))
      (node (ref "C1X") (pin "2") (pinfunction "2_2") (pintype "passive"))
      (node (ref "C1Y") (pin "2") (pinfunction "2_2") (pintype "passive"))
      (node (ref "C1Z") (pin "2") (pinfunction "2_2") (pintype "passive"))
      (node (ref "C2E") (pin "2") (pinfunction "2_2") (pintype "passive"))
      (node (ref "C2X") (pin "2") (pinfunction "2_2") (pintype "passive"))
      (node (ref "C2Y") (pin "2") (pinfunction "2_2") (pintype "passive"))
      (node (ref "C2Z") (pin "2") (pinfunction "2_2") (pintype "passive"))
      (node (ref "C3E") (pin "2") (pinfunction "2_2") (pintype "passive"))
      (node (ref "C3X") (pin "2") (pinfunction "2_2") (pintype "passive"))
      (node (ref "C3Y") (pin "2") (pinfunction "2_2") (pintype "passive"))
      (node (ref "C3Z") (pin "2") (pinfunction "2_2") (pintype "passive"))
      (node (ref "C6E") (pin "1") (pinfunction "1_1") (pintype "passive"))
      (node (ref "C6X") (pin "1") (pinfunction "1_1") (pintype "passive"))
      (node (ref "C6Y") (pin "1") (pinfunction "1_1") (pintype "passive"))
      (node (ref "C6Z") (pin "1") (pinfunction "1_1") (pintype "passive"))
      (node (ref "IC1E") (pin "P19") (pinfunction "VBB1_P19") (pintype "power_in"))
      (node (ref "IC1E") (pin "P24") (pinfunction "VBB2_P24") (pintype "power_in"))
      (node (ref "IC1X") (pin "P19") (pinfunction "VBB1_P19") (pintype "power_in"))
      (node (ref "IC1X") (pin "P24") (pinfunction "VBB2_P24") (pintype "power_in"))
      (node (ref "IC1Y") (pin "P19") (pinfunction "VBB1_P19") (pintype "power_in"))
      (node (ref "IC1Y") (pin "P24") (pinfunction "VBB2_P24") (pintype "power_in"))
      (node (ref "IC1Z") (pin "P19") (pinfunction "VBB1_P19") (pintype "power_in"))
      (node (ref "IC1Z") (pin "P24") (pinfunction "VBB2_P24") (pintype "power_in"))
      (node (ref "J1E") (pin "VMOT") (pinfunction "VMOT_VMOT") (pintype "power_in"))
      (node (ref "J1X") (pin "VMOT") (pinfunction "VMOT_VMOT") (pintype "power_in"))
      (node (ref "J1Y") (pin "VMOT") (pinfunction "VMOT_VMOT") (pintype "power_in"))
      (node (ref "J1Z") (pin "VMOT") (pinfunction "VMOT_VMOT") (pintype "power_in"))
    )
    (net (code "84") (name "unconnected-(J1E-PadMS3)") (class "Default")
      (node (ref "J1E") (pin "MS3") (pinfunction "MS3_MS3") (pintype "bidirectional"))
    )
    (net (code "85") (name "unconnected-(J1X-PadMS3)") (class "Default")
      (node (ref "J1X") (pin "MS3") (pinfunction "MS3_MS3") (pintype "bidirectional"))
    )
    (net (code "86") (name "unconnected-(J1Y-PadMS3)") (class "Default")
      (node (ref "J1Y") (pin "MS3") (pinfunction "MS3_MS3") (pintype "bidirectional"))
    )
    (net (code "87") (name "unconnected-(J1Z-PadMS3)") (class "Default")
      (node (ref "J1Z") (pin "MS3") (pinfunction "MS3_MS3") (pintype "bidirectional"))
    )
  )
)
